# DM1092_LEFT_OV9282.net
KiCad netlist of a schematic drawn in Altium Designer
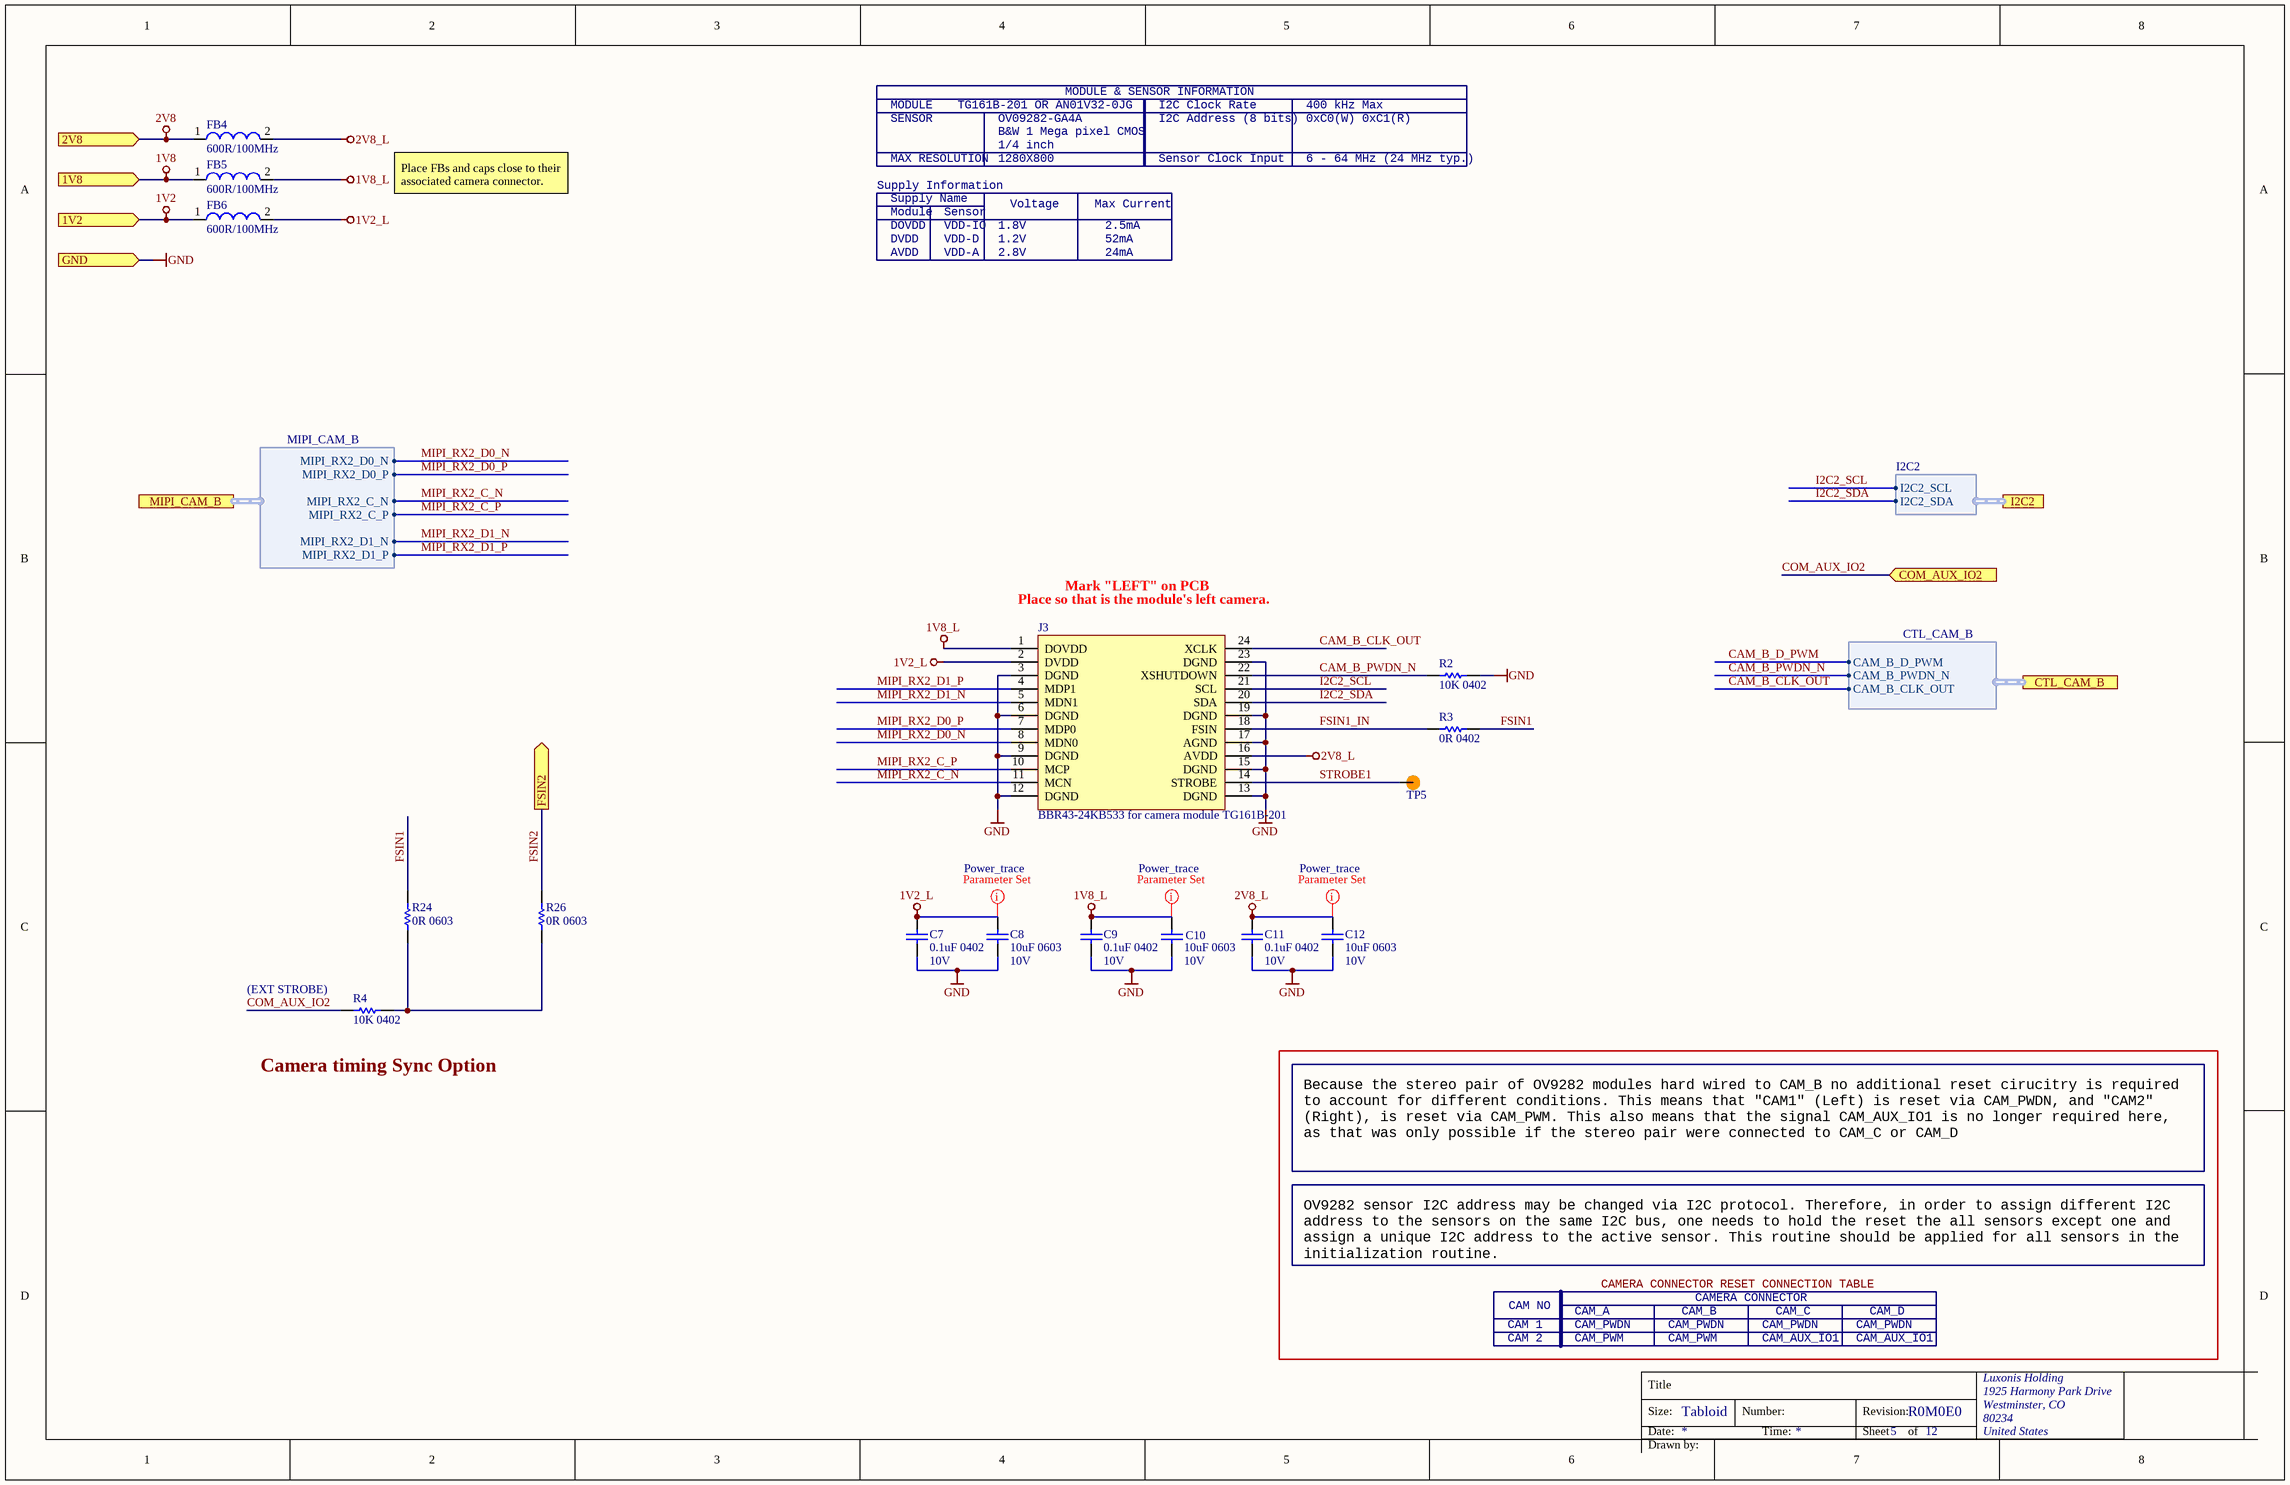
[diagram p0: DM1092_LEFT_OV9282.SchDoc]

(export (version "E")
  (design (tool "Eeschema 10.0.6"))
  (components
    (comp (ref "C7")
      (value "0.1uF 0402")
      (footprint "CAP_Altium_Vault_Generic:CAPC0402(1005)70_L")
      (description "CAP CER 0.1UF 10V X7R 0402 5%")
      (fields (field (name "TOLERANCE") "5%") (field (name "VOLTAGE RATING") "10V"))
      (libsource (lib "LuxonisMaster") (part "GRM155R71A104JA01D"))
    )
    (comp (ref "C8")
      (value "10uF 0603")
      (footprint "CAP_Altium_Vault_Generic:CAPC0603(1608)100_L")
      (description "CAP CER 10UF 10V X5R 0603 20%")
      (fields (field (name "TOLERANCE") "20%") (field (name "VOLTAGE RATING") "10V"))
      (libsource (lib "LuxonisMaster") (part "GRM188R61A106ME69D"))
    )
    (comp (ref "C9")
      (value "0.1uF 0402")
      (footprint "CAP_Altium_Vault_Generic:CAPC0402(1005)70_L")
      (description "CAP CER 0.1UF 10V X7R 0402 5%")
      (fields (field (name "TOLERANCE") "5%") (field (name "VOLTAGE RATING") "10V"))
      (libsource (lib "LuxonisMaster") (part "GRM155R71A104JA01D"))
    )
    (comp (ref "C10")
      (value "10uF 0603")
      (footprint "CAP_Altium_Vault_Generic:CAPC0603(1608)100_L")
      (description "CAP CER 10UF 10V X5R 0603 20%")
      (fields (field (name "TOLERANCE") "20%") (field (name "VOLTAGE RATING") "10V"))
      (libsource (lib "LuxonisMaster") (part "GRM188R61A106ME69D"))
    )
    (comp (ref "C11")
      (value "0.1uF 0402")
      (footprint "CAP_Altium_Vault_Generic:CAPC0402(1005)70_L")
      (description "CAP CER 0.1UF 10V X7R 0402 5%")
      (fields (field (name "TOLERANCE") "5%") (field (name "VOLTAGE RATING") "10V"))
      (libsource (lib "LuxonisMaster") (part "GRM155R71A104JA01D"))
    )
    (comp (ref "C12")
      (value "10uF 0603")
      (footprint "CAP_Altium_Vault_Generic:CAPC0603(1608)100_L")
      (description "CAP CER 10UF 10V X5R 0603 20%")
      (fields (field (name "TOLERANCE") "20%") (field (name "VOLTAGE RATING") "10V"))
      (libsource (lib "LuxonisMaster") (part "GRM188R61A106ME69D"))
    )
    (comp (ref "FB4")
      (value "600R/100MHz")
      (footprint "LuxonisMaster:2508056017Y2")
      (description "FERRITE BEAD, 0.1OHM, 2A, 0805, 600R/100MHz")
      (fields (field (name "TOLERANCE") "25%"))
      (libsource (lib "LuxonisMaster") (part "2508056017Y2"))
    )
    (comp (ref "FB5")
      (value "600R/100MHz")
      (footprint "LuxonisMaster:2508056017Y2")
      (description "FERRITE BEAD, 0.1OHM, 2A, 0805, 600R/100MHz")
      (fields (field (name "TOLERANCE") "25%"))
      (libsource (lib "LuxonisMaster") (part "2508056017Y2"))
    )
    (comp (ref "FB6")
      (value "600R/100MHz")
      (footprint "LuxonisMaster:2508056017Y2")
      (description "FERRITE BEAD, 0.1OHM, 2A, 0805, 600R/100MHz")
      (fields (field (name "TOLERANCE") "25%"))
      (libsource (lib "LuxonisMaster") (part "2508056017Y2"))
    )
    (comp (ref "J3")
      (value "BBR43-24KB533 for camera module TG161B-201")
      (footprint "LuxonisMaster:TG161B-201_HD")
      (description "CONN 24 way, 2 row board to board connector SMD")
      (libsource (lib "LuxonisMaster") (part "TG161B-201_Connector"))
    )
    (comp (ref "R2")
      (value "10K 0402")
      (footprint "RES_Altium_Vault_Generic:RESC0402(1005)_L")
      (fields (field (name "TOLERANCE") "1%"))
      (libsource (lib "LuxonisMaster") (part "RC0402FR-1310KL"))
    )
    (comp (ref "R3")
      (value "0R 0402")
      (footprint "RES_Altium_Vault_Generic:RESC0402(1005)_L")
      (description "RES SMD 0 OHM JUMPER 1/16W 0402")
      (fields (field (name "TOLERANCE") "5%"))
      (libsource (lib "LuxonisMaster") (part "CRCW04020000Z0ED"))
    )
    (comp (ref "R4")
      (value "10K 0402")
      (footprint "RES_Altium_Vault_Generic:RESC0402(1005)_L")
      (fields (field (name "TOLERANCE") "1%"))
      (libsource (lib "LuxonisMaster") (part "RC0402FR-1310KL"))
    )
    (comp (ref "R24")
      (value "0R 0603")
      (footprint "RES_Altium_Vault_Generic:RESC0603(1608)_N")
      (fields (field (name "TOLERANCE") "5%"))
      (libsource (lib "LuxonisMaster") (part "CRCW06030000Z0EA"))
    )
    (comp (ref "R26")
      (value "0R 0603")
      (footprint "RES_Altium_Vault_Generic:RESC0603(1608)_N")
      (fields (field (name "TOLERANCE") "5%"))
      (libsource (lib "LuxonisMaster") (part "CRCW06030000Z0EA"))
    )
    (comp (ref "TP5")
      (value "TP100_200_NS")
      (footprint "LuxonisMaster:TP100_200_NS")
      (libsource (lib "LuxonisMaster") (part "TEST_POINT"))
    )
  )
  (nets
    (net (code "4") (name "/CAM_B_CLK_OUT") (class "Default")
      (node (ref "J3") (pin "24") (pinfunction "XCLK_24") (pintype "passive"))
    )
    (net (code "6") (name "/CAM_B_PWDN_N") (class "Default")
      (node (ref "J3") (pin "22") (pinfunction "XSHUTDOWN_22") (pintype "passive"))
      (node (ref "R2") (pin "1") (pinfunction "1_1") (pintype "passive"))
    )
    (net (code "7") (name "/COM_AUX_IO2") (class "Default")
      (node (ref "R4") (pin "1") (pinfunction "1_1") (pintype "passive"))
    )
    (net (code "8") (name "/FSIN1") (class "Default")
      (node (ref "R24") (pin "2") (pinfunction "2_2") (pintype "passive"))
      (node (ref "R3") (pin "2") (pinfunction "2_2") (pintype "passive"))
    )
    (net (code "9") (name "/FSIN1_IN") (class "Default")
      (node (ref "J3") (pin "18") (pinfunction "FSIN_18") (pintype "passive"))
      (node (ref "R3") (pin "1") (pinfunction "1_1") (pintype "passive"))
    )
    (net (code "10") (name "/FSIN2") (class "Default")
      (node (ref "R26") (pin "2") (pinfunction "2_2") (pintype "passive"))
    )
    (net (code "11") (name "/I2C2_SCL") (class "Default")
      (node (ref "J3") (pin "21") (pinfunction "SCL_21") (pintype "passive"))
    )
    (net (code "12") (name "/I2C2_SDA") (class "Default")
      (node (ref "J3") (pin "20") (pinfunction "SDA_20") (pintype "passive"))
    )
    (net (code "13") (name "/MIPI_RX2_C_N") (class "Default")
      (node (ref "J3") (pin "11") (pinfunction "MCN_11") (pintype "passive"))
    )
    (net (code "14") (name "/MIPI_RX2_C_P") (class "Default")
      (node (ref "J3") (pin "10") (pinfunction "MCP_10") (pintype "passive"))
    )
    (net (code "15") (name "/MIPI_RX2_D0_N") (class "Default")
      (node (ref "J3") (pin "8") (pinfunction "MDN0_8") (pintype "passive"))
    )
    (net (code "16") (name "/MIPI_RX2_D0_P") (class "Default")
      (node (ref "J3") (pin "7") (pinfunction "MDP0_7") (pintype "passive"))
    )
    (net (code "17") (name "/MIPI_RX2_D1_N") (class "Default")
      (node (ref "J3") (pin "5") (pinfunction "MDN1_5") (pintype "passive"))
    )
    (net (code "18") (name "/MIPI_RX2_D1_P") (class "Default")
      (node (ref "J3") (pin "4") (pinfunction "MDP1_4") (pintype "passive"))
    )
    (net (code "19") (name "/STROBE1") (class "Default")
      (node (ref "J3") (pin "14") (pinfunction "STROBE_14") (pintype "passive"))
      (node (ref "TP5") (pin "1") (pintype "passive"))
    )
    (net (code "23") (name "1V2") (class "Default")
      (node (ref "FB6") (pin "1") (pinfunction "1_1") (pintype "passive"))
    )
    (net (code "24") (name "1V2_L") (class "Default")
      (node (ref "C7") (pin "2") (pinfunction "2_2") (pintype "passive"))
      (node (ref "C8") (pin "2") (pinfunction "2_2") (pintype "passive"))
      (node (ref "FB6") (pin "2") (pinfunction "2_2") (pintype "passive"))
      (node (ref "J3") (pin "2") (pinfunction "DVDD_2") (pintype "passive"))
    )
    (net (code "25") (name "1V8") (class "Default")
      (node (ref "FB5") (pin "1") (pinfunction "1_1") (pintype "passive"))
    )
    (net (code "26") (name "1V8_L") (class "Default")
      (node (ref "C10") (pin "2") (pinfunction "2_2") (pintype "passive"))
      (node (ref "C9") (pin "2") (pinfunction "2_2") (pintype "passive"))
      (node (ref "FB5") (pin "2") (pinfunction "2_2") (pintype "passive"))
      (node (ref "J3") (pin "1") (pinfunction "DOVDD_1") (pintype "passive"))
    )
    (net (code "27") (name "2V8") (class "Default")
      (node (ref "FB4") (pin "1") (pinfunction "1_1") (pintype "passive"))
    )
    (net (code "28") (name "2V8_L") (class "Default")
      (node (ref "C11") (pin "2") (pinfunction "2_2") (pintype "passive"))
      (node (ref "C12") (pin "2") (pinfunction "2_2") (pintype "passive"))
      (node (ref "FB4") (pin "2") (pinfunction "2_2") (pintype "passive"))
      (node (ref "J3") (pin "16") (pinfunction "AVDD_16") (pintype "passive"))
    )
    (net (code "29") (name "GND") (class "Default")
      (node (ref "C10") (pin "1") (pinfunction "1_1") (pintype "passive"))
      (node (ref "C11") (pin "1") (pinfunction "1_1") (pintype "passive"))
      (node (ref "C12") (pin "1") (pinfunction "1_1") (pintype "passive"))
      (node (ref "C7") (pin "1") (pinfunction "1_1") (pintype "passive"))
      (node (ref "C8") (pin "1") (pinfunction "1_1") (pintype "passive"))
      (node (ref "C9") (pin "1") (pinfunction "1_1") (pintype "passive"))
      (node (ref "J3") (pin "12") (pinfunction "DGND_12") (pintype "passive"))
      (node (ref "J3") (pin "13") (pinfunction "DGND_13") (pintype "passive"))
      (node (ref "J3") (pin "15") (pinfunction "DGND_15") (pintype "passive"))
      (node (ref "J3") (pin "17") (pinfunction "AGND_17") (pintype "passive"))
      (node (ref "J3") (pin "19") (pinfunction "DGND_19") (pintype "passive"))
      (node (ref "J3") (pin "23") (pinfunction "DGND_23") (pintype "passive"))
      (node (ref "J3") (pin "3") (pinfunction "DGND_3") (pintype "passive"))
      (node (ref "J3") (pin "6") (pinfunction "DGND_6") (pintype "passive"))
      (node (ref "J3") (pin "9") (pinfunction "DGND_9") (pintype "passive"))
      (node (ref "R2") (pin "2") (pinfunction "2_2") (pintype "passive"))
    )
    (net (code "30") (name "Net-(R24-Pad1)") (class "Default")
      (node (ref "R24") (pin "1") (pinfunction "1_1") (pintype "passive"))
      (node (ref "R26") (pin "1") (pinfunction "1_1") (pintype "passive"))
      (node (ref "R4") (pin "2") (pinfunction "2_2") (pintype "passive"))
    )
  )
)
